# SHIELDV2_NANO.net
KiCad netlist of a schematic drawn in EAGLE
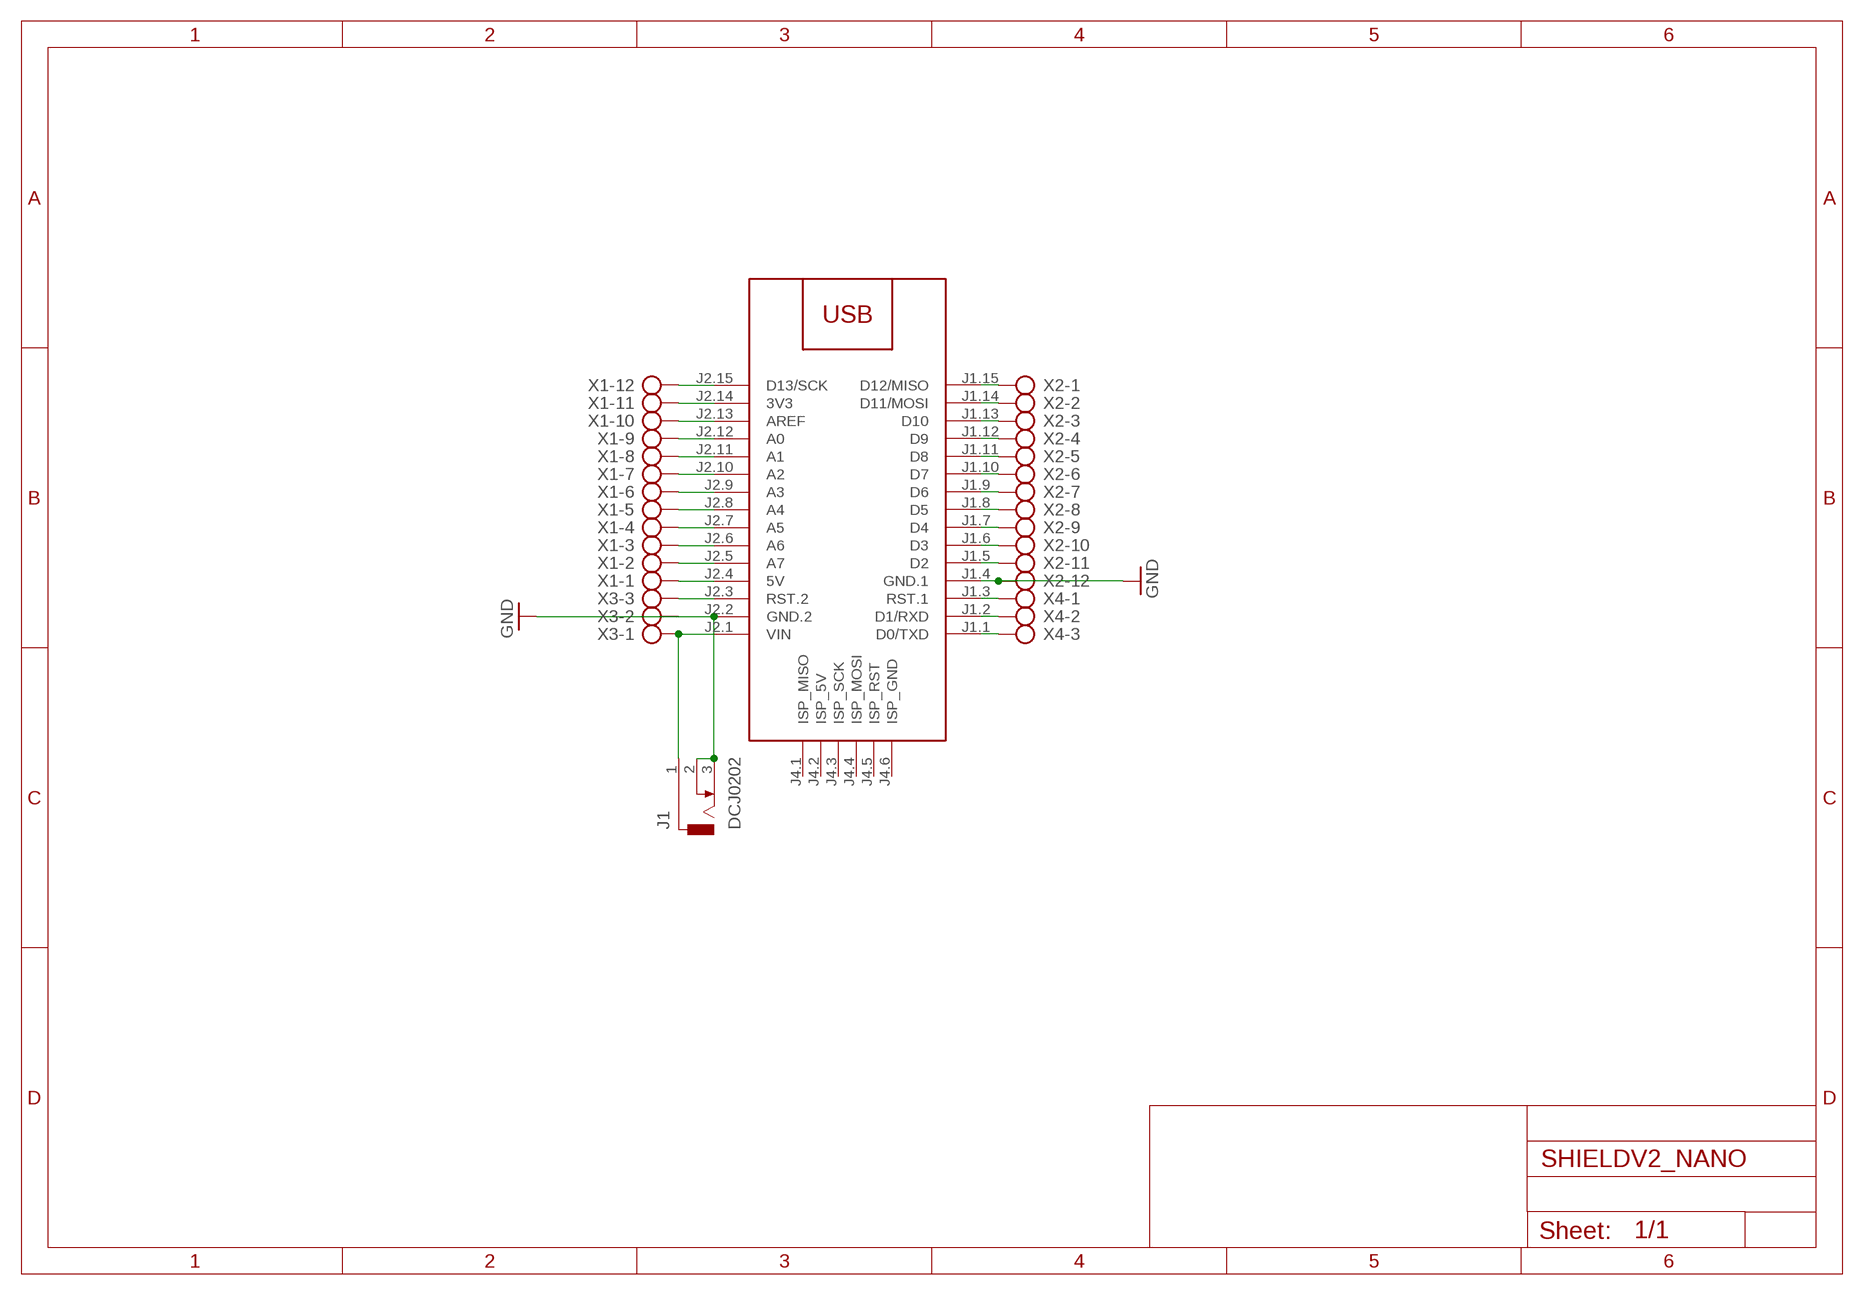
[diagram p0: schematic, sheet 1]

(export (version "E")
  (design (tool "Eeschema 10.0.6"))
  (components
    (comp (ref "J1")
      (value "DCJ0202")
      (footprint "eagle-import:DCJ0202")
      (libsource (lib "eagle-import") (part "DCJ0202"))
    )
    (comp (ref "M1")
      (value "ARDUINO-NANO-3.0#ISP")
      (footprint "eagle-import:ARDUINO-NANO-3.0#ISP")
      (libsource (lib "eagle-import") (part "ARDUINO-NANO-3.0#ISP"))
    )
    (comp (ref "X1")
      (value "AK300/12")
      (footprint "eagle-import:AK300_12")
      (libsource (lib "eagle-import") (part "AK300/12"))
    )
    (comp (ref "X2")
      (value "AK300/12")
      (footprint "eagle-import:AK300_12")
      (libsource (lib "eagle-import") (part "AK300/12"))
    )
    (comp (ref "X3")
      (value "AK300/3")
      (footprint "eagle-import:AK300_3")
      (libsource (lib "eagle-import") (part "AK300/3"))
    )
    (comp (ref "X4")
      (value "AK300/3")
      (footprint "eagle-import:AK300_3")
      (libsource (lib "eagle-import") (part "AK300/3"))
    )
  )
  (nets
    (net (code "1") (name "GND") (class "Default")
      (node (ref "J1") (pin "2") (pinfunction "2_2") (pintype "passive"))
      (node (ref "J1") (pin "3") (pinfunction "3_3") (pintype "passive"))
      (node (ref "M1") (pin "J1.4") (pinfunction "GND.1_J1.4") (pintype "power_in"))
      (node (ref "M1") (pin "J2.2") (pinfunction "GND.2_J2.2") (pintype "power_in"))
      (node (ref "X2") (pin "12") (pinfunction "KL_12") (pintype "passive"))
      (node (ref "X3") (pin "2") (pinfunction "KL_2") (pintype "passive"))
    )
    (net (code "2") (name "Net-(M1-3V3)") (class "Default")
      (node (ref "M1") (pin "J2.14") (pinfunction "3V3_J2.14") (pintype "power_in"))
      (node (ref "X1") (pin "11") (pinfunction "KL_11") (pintype "passive"))
    )
    (net (code "3") (name "Net-(M1-5V)") (class "Default")
      (node (ref "M1") (pin "J2.4") (pinfunction "5V_J2.4") (pintype "power_in"))
      (node (ref "X1") (pin "1") (pinfunction "KL_1") (pintype "passive"))
    )
    (net (code "4") (name "Net-(M1-A0)") (class "Default")
      (node (ref "M1") (pin "J2.12") (pinfunction "A0_J2.12") (pintype "bidirectional"))
      (node (ref "X1") (pin "9") (pinfunction "KL_9") (pintype "passive"))
    )
    (net (code "5") (name "Net-(M1-A1)") (class "Default")
      (node (ref "M1") (pin "J2.11") (pinfunction "A1_J2.11") (pintype "bidirectional"))
      (node (ref "X1") (pin "8") (pinfunction "KL_8") (pintype "passive"))
    )
    (net (code "6") (name "Net-(M1-A2)") (class "Default")
      (node (ref "M1") (pin "J2.10") (pinfunction "A2_J2.10") (pintype "bidirectional"))
      (node (ref "X1") (pin "7") (pinfunction "KL_7") (pintype "passive"))
    )
    (net (code "7") (name "Net-(M1-A3)") (class "Default")
      (node (ref "M1") (pin "J2.9") (pinfunction "A3_J2.9") (pintype "bidirectional"))
      (node (ref "X1") (pin "6") (pinfunction "KL_6") (pintype "passive"))
    )
    (net (code "8") (name "Net-(M1-A4)") (class "Default")
      (node (ref "M1") (pin "J2.8") (pinfunction "A4_J2.8") (pintype "bidirectional"))
      (node (ref "X1") (pin "5") (pinfunction "KL_5") (pintype "passive"))
    )
    (net (code "9") (name "Net-(M1-A5)") (class "Default")
      (node (ref "M1") (pin "J2.7") (pinfunction "A5_J2.7") (pintype "bidirectional"))
      (node (ref "X1") (pin "4") (pinfunction "KL_4") (pintype "passive"))
    )
    (net (code "10") (name "Net-(M1-A6)") (class "Default")
      (node (ref "M1") (pin "J2.6") (pinfunction "A6_J2.6") (pintype "bidirectional"))
      (node (ref "X1") (pin "3") (pinfunction "KL_3") (pintype "passive"))
    )
    (net (code "11") (name "Net-(M1-A7)") (class "Default")
      (node (ref "M1") (pin "J2.5") (pinfunction "A7_J2.5") (pintype "bidirectional"))
      (node (ref "X1") (pin "2") (pinfunction "KL_2") (pintype "passive"))
    )
    (net (code "12") (name "Net-(M1-AREF)") (class "Default")
      (node (ref "M1") (pin "J2.13") (pinfunction "AREF_J2.13") (pintype "bidirectional"))
      (node (ref "X1") (pin "10") (pinfunction "KL_10") (pintype "passive"))
    )
    (net (code "13") (name "Net-(M1-D0{slash}TXD)") (class "Default")
      (node (ref "M1") (pin "J1.1") (pinfunction "D0/TXD_J1.1") (pintype "bidirectional"))
      (node (ref "X4") (pin "3") (pinfunction "KL_3") (pintype "passive"))
    )
    (net (code "14") (name "Net-(M1-D1{slash}RXD)") (class "Default")
      (node (ref "M1") (pin "J1.2") (pinfunction "D1/RXD_J1.2") (pintype "bidirectional"))
      (node (ref "X4") (pin "2") (pinfunction "KL_2") (pintype "passive"))
    )
    (net (code "15") (name "Net-(M1-D2)") (class "Default")
      (node (ref "M1") (pin "J1.5") (pinfunction "D2_J1.5") (pintype "bidirectional"))
      (node (ref "X2") (pin "11") (pinfunction "KL_11") (pintype "passive"))
    )
    (net (code "16") (name "Net-(M1-D3)") (class "Default")
      (node (ref "M1") (pin "J1.6") (pinfunction "D3_J1.6") (pintype "bidirectional"))
      (node (ref "X2") (pin "10") (pinfunction "KL_10") (pintype "passive"))
    )
    (net (code "17") (name "Net-(M1-D4)") (class "Default")
      (node (ref "M1") (pin "J1.7") (pinfunction "D4_J1.7") (pintype "bidirectional"))
      (node (ref "X2") (pin "9") (pinfunction "KL_9") (pintype "passive"))
    )
    (net (code "18") (name "Net-(M1-D5)") (class "Default")
      (node (ref "M1") (pin "J1.8") (pinfunction "D5_J1.8") (pintype "bidirectional"))
      (node (ref "X2") (pin "8") (pinfunction "KL_8") (pintype "passive"))
    )
    (net (code "19") (name "Net-(M1-D6)") (class "Default")
      (node (ref "M1") (pin "J1.9") (pinfunction "D6_J1.9") (pintype "bidirectional"))
      (node (ref "X2") (pin "7") (pinfunction "KL_7") (pintype "passive"))
    )
    (net (code "20") (name "Net-(M1-D7)") (class "Default")
      (node (ref "M1") (pin "J1.10") (pinfunction "D7_J1.10") (pintype "bidirectional"))
      (node (ref "X2") (pin "6") (pinfunction "KL_6") (pintype "passive"))
    )
    (net (code "21") (name "Net-(M1-D8)") (class "Default")
      (node (ref "M1") (pin "J1.11") (pinfunction "D8_J1.11") (pintype "bidirectional"))
      (node (ref "X2") (pin "5") (pinfunction "KL_5") (pintype "passive"))
    )
    (net (code "22") (name "Net-(M1-D9)") (class "Default")
      (node (ref "M1") (pin "J1.12") (pinfunction "D9_J1.12") (pintype "bidirectional"))
      (node (ref "X2") (pin "4") (pinfunction "KL_4") (pintype "passive"))
    )
    (net (code "23") (name "Net-(M1-D10)") (class "Default")
      (node (ref "M1") (pin "J1.13") (pinfunction "D10_J1.13") (pintype "bidirectional"))
      (node (ref "X2") (pin "3") (pinfunction "KL_3") (pintype "passive"))
    )
    (net (code "24") (name "Net-(M1-D11{slash}MOSI)") (class "Default")
      (node (ref "M1") (pin "J1.14") (pinfunction "D11/MOSI_J1.14") (pintype "bidirectional"))
      (node (ref "X2") (pin "2") (pinfunction "KL_2") (pintype "passive"))
    )
    (net (code "25") (name "Net-(M1-D12{slash}MISO)") (class "Default")
      (node (ref "M1") (pin "J1.15") (pinfunction "D12/MISO_J1.15") (pintype "bidirectional"))
      (node (ref "X2") (pin "1") (pinfunction "KL_1") (pintype "passive"))
    )
    (net (code "26") (name "Net-(M1-D13{slash}SCK)") (class "Default")
      (node (ref "M1") (pin "J2.15") (pinfunction "D13/SCK_J2.15") (pintype "bidirectional"))
      (node (ref "X1") (pin "12") (pinfunction "KL_12") (pintype "passive"))
    )
    (net (code "27") (name "Net-(M1-RST.1)") (class "Default")
      (node (ref "M1") (pin "J1.3") (pinfunction "RST.1_J1.3") (pintype "bidirectional"))
      (node (ref "X4") (pin "1") (pinfunction "KL_1") (pintype "passive"))
    )
    (net (code "28") (name "Net-(M1-RST.2)") (class "Default")
      (node (ref "M1") (pin "J2.3") (pinfunction "RST.2_J2.3") (pintype "bidirectional"))
      (node (ref "X3") (pin "3") (pinfunction "KL_3") (pintype "passive"))
    )
    (net (code "29") (name "Net-(M1-VIN)") (class "Default")
      (node (ref "J1") (pin "1") (pinfunction "1_1") (pintype "passive"))
      (node (ref "M1") (pin "J2.1") (pinfunction "VIN_J2.1") (pintype "power_in"))
      (node (ref "X3") (pin "1") (pinfunction "KL_1") (pintype "passive"))
    )
    (net (code "30") (name "unconnected-(M1-ISP_5V-PadJ4.2)") (class "Default")
      (node (ref "M1") (pin "J4.2") (pinfunction "ISP_5V_J4.2") (pintype "bidirectional"))
    )
    (net (code "31") (name "unconnected-(M1-ISP_GND-PadJ4.6)") (class "Default")
      (node (ref "M1") (pin "J4.6") (pinfunction "ISP_GND_J4.6") (pintype "bidirectional"))
    )
    (net (code "32") (name "unconnected-(M1-ISP_MISO-PadJ4.1)") (class "Default")
      (node (ref "M1") (pin "J4.1") (pinfunction "ISP_MISO_J4.1") (pintype "bidirectional"))
    )
    (net (code "33") (name "unconnected-(M1-ISP_MOSI-PadJ4.4)") (class "Default")
      (node (ref "M1") (pin "J4.4") (pinfunction "ISP_MOSI_J4.4") (pintype "bidirectional"))
    )
    (net (code "34") (name "unconnected-(M1-ISP_RST-PadJ4.5)") (class "Default")
      (node (ref "M1") (pin "J4.5") (pinfunction "ISP_RST_J4.5") (pintype "bidirectional"))
    )
    (net (code "35") (name "unconnected-(M1-ISP_SCK-PadJ4.3)") (class "Default")
      (node (ref "M1") (pin "J4.3") (pinfunction "ISP_SCK_J4.3") (pintype "bidirectional"))
    )
  )
)
